# SOC_CAM.net
KiCad netlist of a schematic drawn in Altium Designer
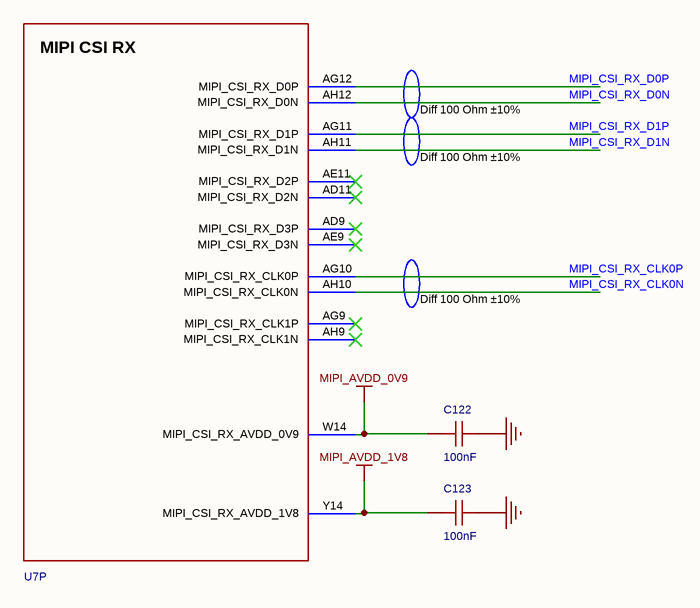
[diagram p0: SOC_CAM.schdoc]

(export (version "E")
  (design (tool "Eeschema 10.0.6"))
  (components
    (comp (ref "C122")
      (value "100nF")
      (footprint "C0201")
      (description "容值:4.7uF;精度:±20%;额定电压:6.3V;温度系数:X5R;")
      (fields
        (field (name "MANUFACTURER") "muRata(村田)")
        (field (name "MANUFACTURERPART") "GRM035R60J475ME15D")
      )
      (libsource (lib "altium-import") (part "root_1_GRM035R60J475ME15D_"))
    )
    (comp (ref "C123")
      (value "100nF")
      (footprint "C0201")
      (description "容值:4.7uF;精度:±20%;额定电压:6.3V;温度系数:X5R;")
      (fields
        (field (name "MANUFACTURER") "muRata(村田)")
        (field (name "MANUFACTURERPART") "GRM035R60J475ME15D")
      )
      (libsource (lib "altium-import") (part "root_1_GRM035R60J475ME15D_"))
    )
    (comp (ref "U7")
      (value "RK3568")
      (footprint "BGA-636_L19.0-W19.0-P0.65-BL")
      (libsource (lib "altium-import") (part "root_0_RK3568_"))
    )
  )
  (nets
    (net (code "1") (name "/MIPI_CSI_RX_CLK0N") (class "Default")
      (node (ref "U7") (pin "AH10") (pinfunction "MIPI_CSI_RX_CLK0N_AH10") (pintype "passive"))
    )
    (net (code "2") (name "/MIPI_CSI_RX_CLK0P") (class "Default")
      (node (ref "U7") (pin "AG10") (pinfunction "MIPI_CSI_RX_CLK0P_AG10") (pintype "passive"))
    )
    (net (code "3") (name "/MIPI_CSI_RX_D0N") (class "Default")
      (node (ref "U7") (pin "AH12") (pinfunction "MIPI_CSI_RX_D0N_AH12") (pintype "passive"))
    )
    (net (code "4") (name "/MIPI_CSI_RX_D0P") (class "Default")
      (node (ref "U7") (pin "AG12") (pinfunction "MIPI_CSI_RX_D0P_AG12") (pintype "passive"))
    )
    (net (code "5") (name "/MIPI_CSI_RX_D1N") (class "Default")
      (node (ref "U7") (pin "AH11") (pinfunction "MIPI_CSI_RX_D1N_AH11") (pintype "passive"))
    )
    (net (code "6") (name "/MIPI_CSI_RX_D1P") (class "Default")
      (node (ref "U7") (pin "AG11") (pinfunction "MIPI_CSI_RX_D1P_AG11") (pintype "passive"))
    )
    (net (code "7") (name "GND") (class "Default")
      (node (ref "C122") (pin "1") (pinfunction "1_1") (pintype "passive"))
      (node (ref "C123") (pin "1") (pinfunction "1_1") (pintype "passive"))
    )
    (net (code "8") (name "MIPI_AVDD_0V9") (class "Default")
      (node (ref "C122") (pin "2") (pinfunction "2_2") (pintype "passive"))
      (node (ref "U7") (pin "W14") (pinfunction "MIPI_CSI_RX_AVDD_0V9_W14") (pintype "passive"))
    )
    (net (code "9") (name "MIPI_AVDD_1V8") (class "Default")
      (node (ref "C123") (pin "2") (pinfunction "2_2") (pintype "passive"))
      (node (ref "U7") (pin "Y14") (pinfunction "MIPI_CSI_RX_AVDD_1V8_Y14") (pintype "passive"))
    )
    (net (code "10") (name "unconnected-(U7P-MIPI_CSI_RX_CLK1N-PadAH9)") (class "Default")
      (node (ref "U7") (pin "AH9") (pinfunction "MIPI_CSI_RX_CLK1N_AH9") (pintype "passive+no_connect"))
    )
    (net (code "11") (name "unconnected-(U7P-MIPI_CSI_RX_CLK1P-PadAG9)") (class "Default")
      (node (ref "U7") (pin "AG9") (pinfunction "MIPI_CSI_RX_CLK1P_AG9") (pintype "passive+no_connect"))
    )
    (net (code "12") (name "unconnected-(U7P-MIPI_CSI_RX_D2N-PadAD11)") (class "Default")
      (node (ref "U7") (pin "AD11") (pinfunction "MIPI_CSI_RX_D2N_AD11") (pintype "passive+no_connect"))
    )
    (net (code "13") (name "unconnected-(U7P-MIPI_CSI_RX_D2P-PadAE11)") (class "Default")
      (node (ref "U7") (pin "AE11") (pinfunction "MIPI_CSI_RX_D2P_AE11") (pintype "passive+no_connect"))
    )
    (net (code "14") (name "unconnected-(U7P-MIPI_CSI_RX_D3N-PadAE9)") (class "Default")
      (node (ref "U7") (pin "AE9") (pinfunction "MIPI_CSI_RX_D3N_AE9") (pintype "passive+no_connect"))
    )
    (net (code "15") (name "unconnected-(U7P-MIPI_CSI_RX_D3P-PadAD9)") (class "Default")
      (node (ref "U7") (pin "AD9") (pinfunction "MIPI_CSI_RX_D3P_AD9") (pintype "passive+no_connect"))
    )
  )
)
